# Electronic_Load_Top.net
KiCad netlist of a schematic drawn in Altium Designer
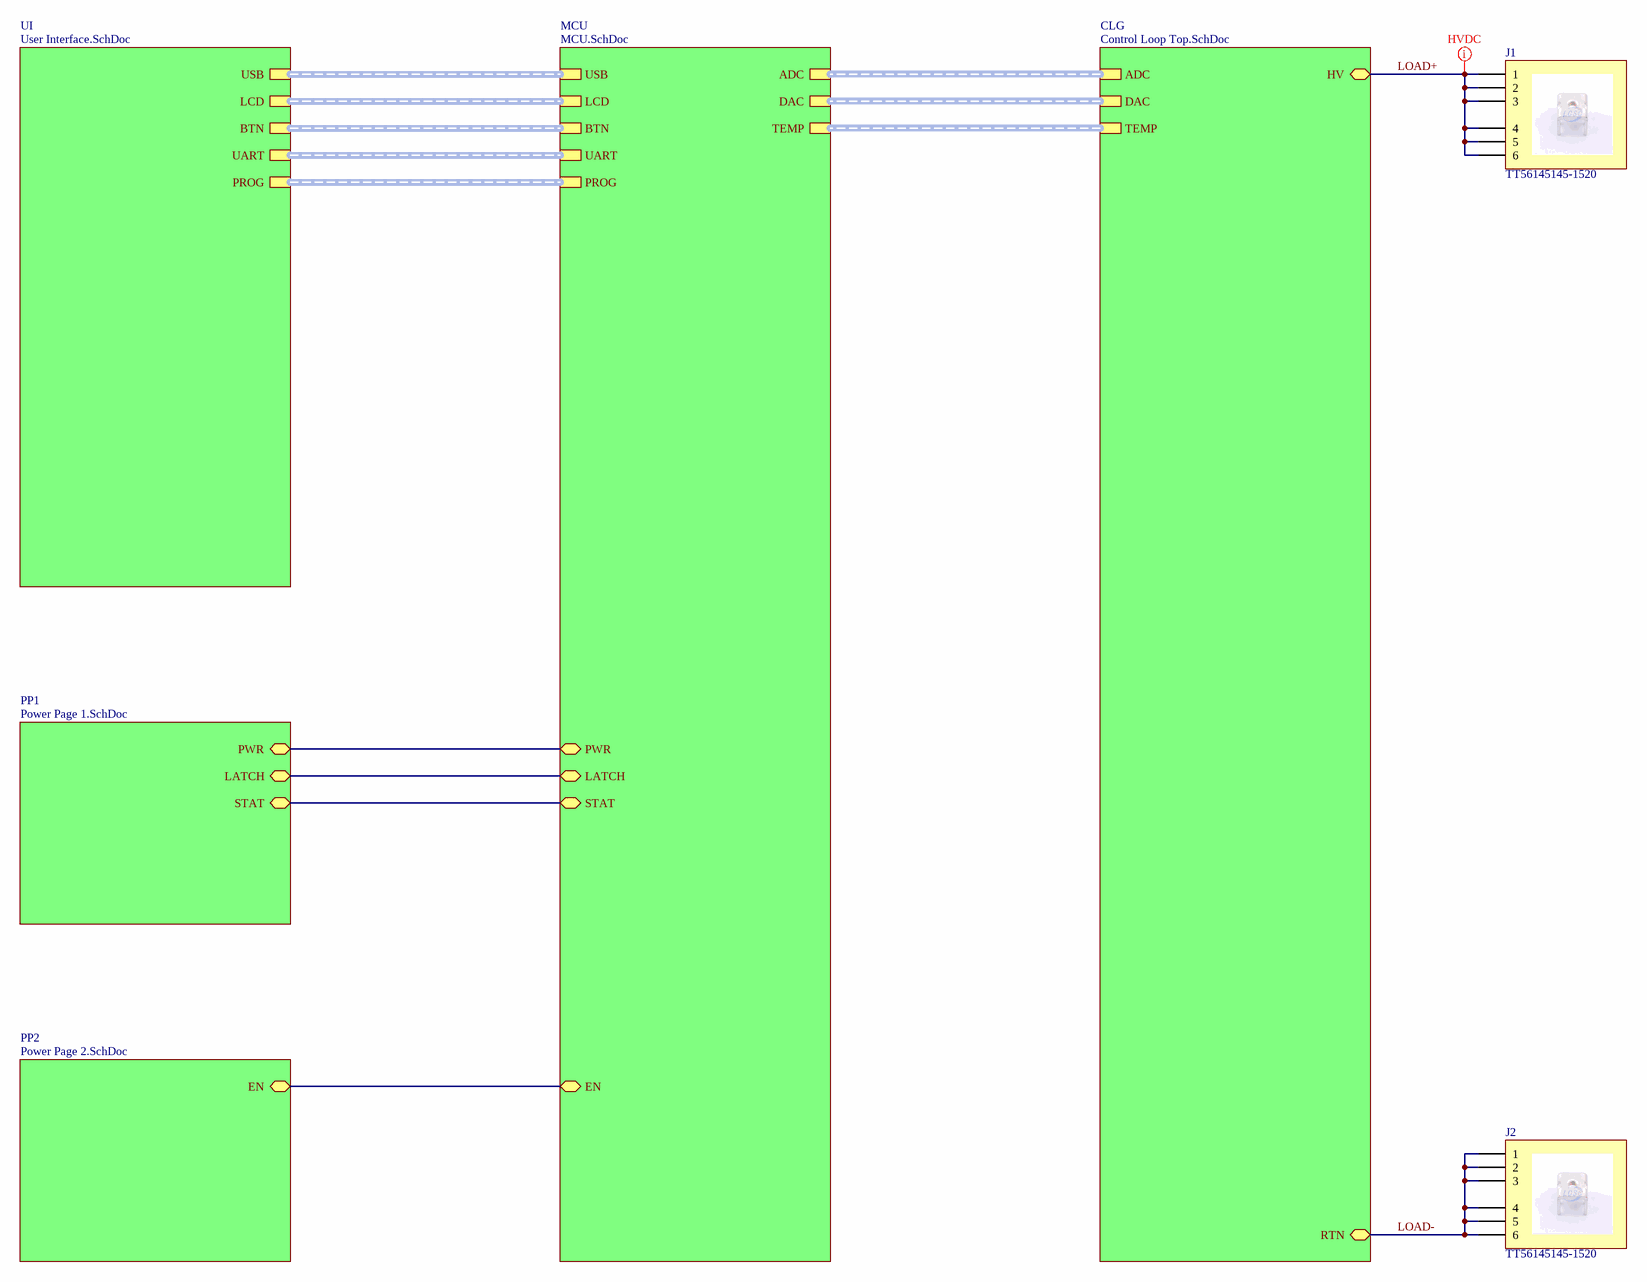
[diagram p0: Electronic Load Top.SchDoc]

(export (version "E")
  (design (tool "Eeschema 10.0.6"))
  (components
    (comp (ref "J1")
      (value "TT56145145-1520")
      (footprint "XFCN_TT56145145-1520")
      (description "6 M5 Through Hole Screw Connectors ROHS")
      (fields (field (name "VENDOR 1 PART NUMBER") "C19724595") (field (name "CREATEDBY") "Judd Foster"))
      (libsource (lib "Component Library") (part "Term,Screw,M5,Top,Thru"))
    )
    (comp (ref "J2")
      (value "TT56145145-1520")
      (footprint "XFCN_TT56145145-1520")
      (description "6 M5 Through Hole Screw Connectors ROHS")
      (fields (field (name "VENDOR 1 PART NUMBER") "C19724595") (field (name "CREATEDBY") "Judd Foster"))
      (libsource (lib "Component Library") (part "Term,Screw,M5,Top,Thru"))
    )
  )
  (nets
    (net (code "7") (name "/LOAD+") (class "Default")
      (node (ref "J1") (pin "1") (pinfunction "1_1") (pintype "passive"))
      (node (ref "J1") (pin "2") (pinfunction "2_2") (pintype "passive"))
      (node (ref "J1") (pin "3") (pinfunction "3_3") (pintype "passive"))
      (node (ref "J1") (pin "4") (pinfunction "4_4") (pintype "passive"))
      (node (ref "J1") (pin "5") (pinfunction "5_5") (pintype "passive"))
      (node (ref "J1") (pin "6") (pinfunction "6_6") (pintype "passive"))
    )
    (net (code "8") (name "/LOAD-") (class "Default")
      (node (ref "J2") (pin "1") (pinfunction "1_1") (pintype "passive"))
      (node (ref "J2") (pin "2") (pinfunction "2_2") (pintype "passive"))
      (node (ref "J2") (pin "3") (pinfunction "3_3") (pintype "passive"))
      (node (ref "J2") (pin "4") (pinfunction "4_4") (pintype "passive"))
      (node (ref "J2") (pin "5") (pinfunction "5_5") (pintype "passive"))
      (node (ref "J2") (pin "6") (pinfunction "6_6") (pintype "passive"))
    )
  )
)
